# OpenMPPT2-CAN.net
KiCad netlist of a schematic drawn in Altium Designer
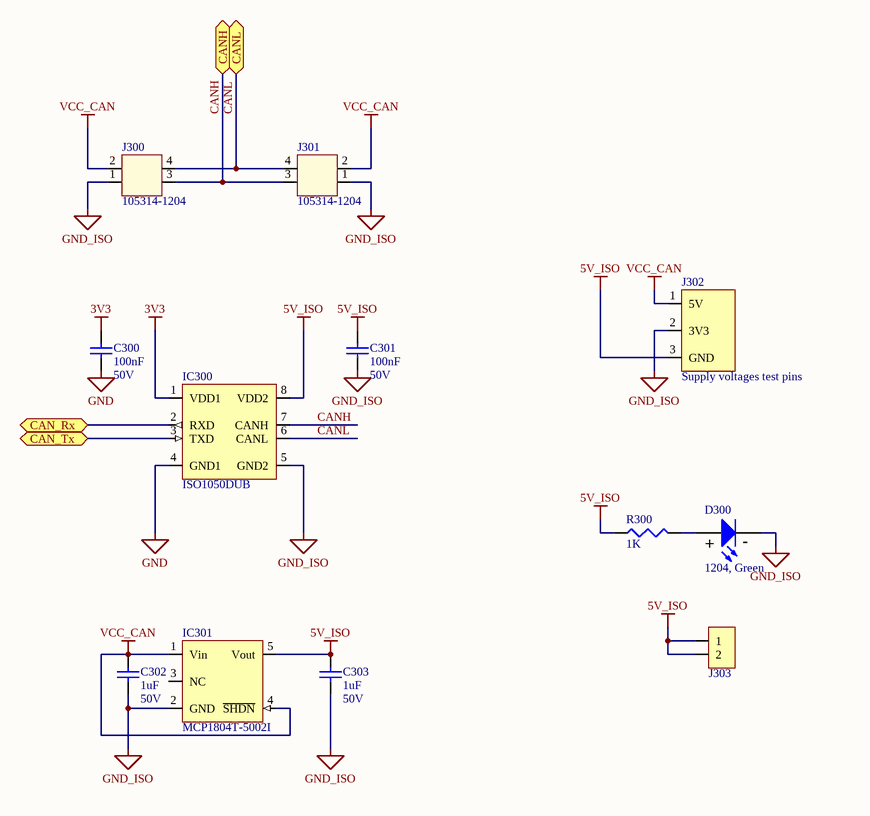
[diagram p0: OpenMPPT2-CAN.SchDoc]

(export (version "E")
  (design (tool "Eeschema 10.0.6"))
  (components
    (comp (ref "C300")
      (value "100nF")
      (footprint "C0603")
      (description "Capacitor, 100nF, 50V, X7R")
      (fields (field (name "VOLTAGE RATING") "50V"))
      (libsource (lib "SBT_Capacitors_Ceramic") (part "100nF/0603/CER/50V"))
    )
    (comp (ref "C301")
      (value "100nF")
      (footprint "C0603")
      (description "Capacitor, 100nF, 50V, X7R")
      (fields (field (name "VOLTAGE RATING") "50V"))
      (libsource (lib "SBT_Capacitors_Ceramic") (part "100nF/0603/CER/50V"))
    )
    (comp (ref "C302")
      (value "1uF")
      (footprint "C-0805")
      (description "Capacitor, 1uF, 50V,  X7R")
      (fields (field (name "VOLTAGE RATING") "50V"))
      (libsource (lib "SBT_Capacitors_Ceramic") (part "1uF/0805/CER/50V"))
    )
    (comp (ref "C303")
      (value "1uF")
      (footprint "C-0805")
      (description "Capacitor, 1uF, 50V,  X7R")
      (fields (field (name "VOLTAGE RATING") "50V"))
      (libsource (lib "SBT_Capacitors_Ceramic") (part "1uF/0805/CER/50V"))
    )
    (comp (ref "D300")
      (value "1204, Green")
      (footprint "WL-SMSW, 1204")
      (description "WL-SMSW SMD chip LED side view mono-color waterclear, size 1204, Green")
      (fields (field (name "PARTNUMBER") "155124GS73200") (field (name "PUBLISHER") "Wurth Elektronik"))
      (libsource (lib "ALTIUM-WL-SMSW-rev16b") (part "155124GS73200"))
    )
    (comp (ref "IC300")
      (value "ISO1050DUB")
      (footprint "DUB (P-DSO-G8)")
      (description "CAN TRANSCEIVER")
      (libsource (lib "SBT_ICs") (part "ISO1050DUB"))
    )
    (comp (ref "IC301")
      (value "MCP1804T-5002I")
      (footprint "SOT-23-5")
      (description "LDO, Fixed, 5V, 150mA")
      (libsource (lib "SBT_ICs") (part "MCP1804T-5002I"))
    )
    (comp (ref "J300")
      (value "105314-1204")
      (footprint "Nano-Fit 4p RA")
      (description "Molex nano-fit 4 pins connector, dual row, right angle")
      (libsource (lib "") (part "105314-1204_1"))
    )
    (comp (ref "J301")
      (value "105314-1204")
      (footprint "Nano-Fit 4p RA")
      (description "Molex nano-fit 4 pins connector, dual row, right angle")
      (libsource (lib "SBT_Connectors") (part "105314-1204"))
    )
    (comp (ref "J302")
      (value "Supply voltages test pins")
      (footprint "Header 2.54 3p")
      (description "Standard 2.54mm pins for 5V, 3V3, and GND")
      (libsource (lib "SBT_Connectors") (part "Supply voltages test pins"))
    )
    (comp (ref "J303")
      (value "2p male right angle header")
      (footprint "2P Angled Header Male, THT")
      (description "2p 2.54mm male right angle header")
      (libsource (lib "SBT_Connectors") (part "2p male right angle header"))
    )
    (comp (ref "R300")
      (value "1K")
      (footprint "0603")
      (description "Resistor, 1K, 1%, 0.063W, 50V, 100PPM, 0603")
      (libsource (lib "SBT_Resistors_SMD") (part "1K/0603/0063W/50V"))
    )
  )
  (nets
    (net (code "1") (name "/CANH") (class "Default")
      (node (ref "IC300") (pin "7") (pinfunction "CANH_7") (pintype "bidirectional"))
      (node (ref "J300") (pin "3") (pinfunction "3_3") (pintype "passive"))
      (node (ref "J301") (pin "3") (pinfunction "3_3") (pintype "passive"))
    )
    (net (code "2") (name "/CANL") (class "Default")
      (node (ref "IC300") (pin "6") (pinfunction "CANL_6") (pintype "bidirectional"))
      (node (ref "J300") (pin "4") (pinfunction "4_4") (pintype "passive"))
      (node (ref "J301") (pin "4") (pinfunction "4_4") (pintype "passive"))
    )
    (net (code "3") (name "/CAN_Rx") (class "Default")
      (node (ref "IC300") (pin "2") (pinfunction "RXD_2") (pintype "output"))
    )
    (net (code "4") (name "/CAN_Tx") (class "Default")
      (node (ref "IC300") (pin "3") (pinfunction "TXD_3") (pintype "input"))
    )
    (net (code "5") (name "3V3") (class "Default")
      (node (ref "C300") (pin "2") (pinfunction "2_2") (pintype "passive"))
      (node (ref "IC300") (pin "1") (pinfunction "VDD1_1") (pintype "power_in"))
    )
    (net (code "6") (name "5V_ISO") (class "Default")
      (node (ref "C301") (pin "2") (pinfunction "2_2") (pintype "passive"))
      (node (ref "C303") (pin "1") (pinfunction "1_1") (pintype "passive"))
      (node (ref "IC300") (pin "8") (pinfunction "VDD2_8") (pintype "power_in"))
      (node (ref "IC301") (pin "5") (pinfunction "Vout_5") (pintype "power_in"))
      (node (ref "J302") (pin "3") (pinfunction "GND_3") (pintype "passive"))
      (node (ref "J303") (pin "1") (pinfunction "1_1") (pintype "passive"))
      (node (ref "J303") (pin "2") (pinfunction "2_2") (pintype "passive"))
      (node (ref "R300") (pin "1") (pinfunction "1_1") (pintype "passive"))
    )
    (net (code "7") (name "GND") (class "Default")
      (node (ref "C300") (pin "1") (pinfunction "1_1") (pintype "passive"))
      (node (ref "IC300") (pin "4") (pinfunction "GND1_4") (pintype "power_in"))
    )
    (net (code "8") (name "GND_ISO") (class "Default")
      (node (ref "C301") (pin "1") (pinfunction "1_1") (pintype "passive"))
      (node (ref "C302") (pin "2") (pinfunction "2_2") (pintype "passive"))
      (node (ref "C303") (pin "2") (pinfunction "2_2") (pintype "passive"))
      (node (ref "D300") (pin "1") (pinfunction "1_1") (pintype "passive"))
      (node (ref "IC300") (pin "5") (pinfunction "GND2_5") (pintype "power_in"))
      (node (ref "IC301") (pin "2") (pinfunction "GND_2") (pintype "power_in"))
      (node (ref "J300") (pin "1") (pinfunction "1_1") (pintype "passive"))
      (node (ref "J301") (pin "1") (pinfunction "1_1") (pintype "passive"))
      (node (ref "J302") (pin "2") (pinfunction "3V3_2") (pintype "passive"))
    )
    (net (code "9") (name "Net-(D300-Pad2)") (class "Default")
      (node (ref "D300") (pin "2") (pinfunction "2_2") (pintype "passive"))
      (node (ref "R300") (pin "2") (pinfunction "2_2") (pintype "passive"))
    )
    (net (code "10") (name "VCC_CAN") (class "Default")
      (node (ref "C302") (pin "1") (pinfunction "1_1") (pintype "passive"))
      (node (ref "IC301") (pin "1") (pinfunction "Vin_1") (pintype "power_in"))
      (node (ref "IC301") (pin "4") (pinfunction "~{SHDN}_4") (pintype "input"))
      (node (ref "J300") (pin "2") (pinfunction "2_2") (pintype "passive"))
      (node (ref "J301") (pin "2") (pinfunction "2_2") (pintype "passive"))
      (node (ref "J302") (pin "1") (pinfunction "5V_1") (pintype "passive"))
    )
    (net (code "11") (name "unconnected-(IC301-NC-Pad3)") (class "Default")
      (node (ref "IC301") (pin "3") (pinfunction "NC_3") (pintype "passive"))
    )
  )
)
